# Button.net
KiCad netlist of a schematic drawn in Altium Designer
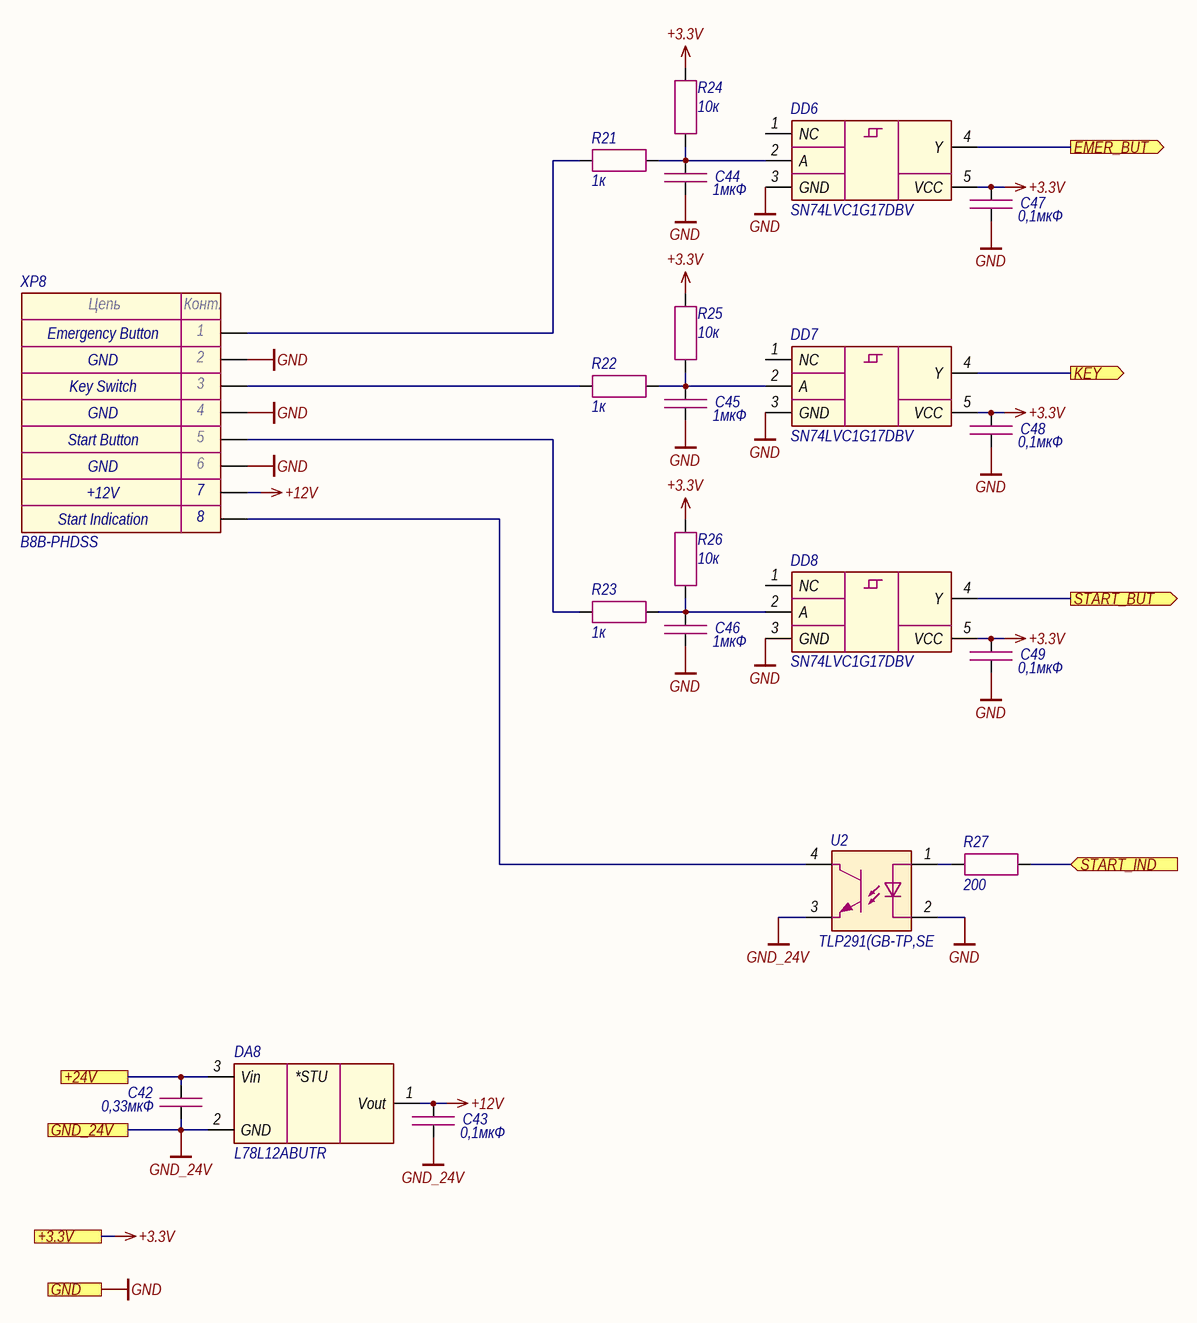
[diagram p0: Button.SchDoc]

(export (version "E")
  (design (tool "Eeschema 10.0.6"))
  (components
    (comp (ref "C42")
      (value "0,33мкФ")
      (footprint "Pcb_library:CAP_0805")
      (fields (field (name "MANUFACTURER") "Murata"))
      (libsource (lib "Schem_library") (part "Capacitor"))
    )
    (comp (ref "C43")
      (value "0,1мкФ")
      (footprint "Pcb_library:CAP_0603")
      (fields (field (name "MANUFACTURER") "Murata"))
      (libsource (lib "Schem_library") (part "Capacitor"))
    )
    (comp (ref "C44")
      (value "1мкФ")
      (footprint "Pcb_library:CAP_0603")
      (fields (field (name "MANUFACTURER") "Murata"))
      (libsource (lib "Schem_library") (part "Capacitor"))
    )
    (comp (ref "C45")
      (value "1мкФ")
      (footprint "Pcb_library:CAP_0603")
      (fields (field (name "MANUFACTURER") "Murata"))
      (libsource (lib "Schem_library") (part "Capacitor"))
    )
    (comp (ref "C46")
      (value "1мкФ")
      (footprint "Pcb_library:CAP_0603")
      (fields (field (name "MANUFACTURER") "Murata"))
      (libsource (lib "Schem_library") (part "Capacitor"))
    )
    (comp (ref "C47")
      (value "0,1мкФ")
      (footprint "Pcb_library:CAP_0603")
      (fields (field (name "MANUFACTURER") "Murata"))
      (libsource (lib "Schem_library") (part "Capacitor"))
    )
    (comp (ref "C48")
      (value "0,1мкФ")
      (footprint "Pcb_library:CAP_0603")
      (fields (field (name "MANUFACTURER") "Murata"))
      (libsource (lib "Schem_library") (part "Capacitor"))
    )
    (comp (ref "C49")
      (value "0,1мкФ")
      (footprint "Pcb_library:CAP_0603")
      (fields (field (name "MANUFACTURER") "Murata"))
      (libsource (lib "Schem_library") (part "Capacitor"))
    )
    (comp (ref "DA8")
      (value "L78L12ABUTR")
      (footprint "Pcb_library:SOT-89")
      (fields (field (name "MANUFACTURER") "STMicroelectronics"))
      (libsource (lib "Schem_library") (part "LD2981ABU50TR"))
    )
    (comp (ref "DD6")
      (value "SN74LVC1G17DBV")
      (footprint "Pcb_library:SOT-23-5")
      (fields (field (name "MANUFACTURER") "Texas Instruments"))
      (libsource (lib "Schem_library") (part "SN74LVC1G17"))
    )
    (comp (ref "DD7")
      (value "SN74LVC1G17DBV")
      (footprint "Pcb_library:SOT-23-5")
      (fields (field (name "MANUFACTURER") "Texas Instruments"))
      (libsource (lib "Schem_library") (part "SN74LVC1G17"))
    )
    (comp (ref "DD8")
      (value "SN74LVC1G17DBV")
      (footprint "Pcb_library:SOT-23-5")
      (fields (field (name "MANUFACTURER") "Texas Instruments"))
      (libsource (lib "Schem_library") (part "SN74LVC1G17"))
    )
    (comp (ref "R21")
      (value "1к")
      (footprint "Pcb_library:RES_0603")
      (fields (field (name "MANUFACTURER") "Yageo"))
      (libsource (lib "Schem_library") (part "Resistor"))
    )
    (comp (ref "R22")
      (value "1к")
      (footprint "Pcb_library:RES_0603")
      (fields (field (name "MANUFACTURER") "Yageo"))
      (libsource (lib "Schem_library") (part "Resistor"))
    )
    (comp (ref "R23")
      (value "1к")
      (footprint "Pcb_library:RES_0603")
      (fields (field (name "MANUFACTURER") "Yageo"))
      (libsource (lib "Schem_library") (part "Resistor"))
    )
    (comp (ref "R24")
      (value "10к")
      (footprint "Pcb_library:RES_0603")
      (fields (field (name "MANUFACTURER") "Yageo"))
      (libsource (lib "Schem_library") (part "Resistor"))
    )
    (comp (ref "R25")
      (value "10к")
      (footprint "Pcb_library:RES_0603")
      (fields (field (name "MANUFACTURER") "Yageo"))
      (libsource (lib "Schem_library") (part "Resistor"))
    )
    (comp (ref "R26")
      (value "10к")
      (footprint "Pcb_library:RES_0603")
      (fields (field (name "MANUFACTURER") "Yageo"))
      (libsource (lib "Schem_library") (part "Resistor"))
    )
    (comp (ref "R27")
      (value "200")
      (footprint "Pcb_library:RES_0603")
      (fields (field (name "MANUFACTURER") "Yageo"))
      (libsource (lib "Schem_library") (part "Resistor"))
    )
    (comp (ref "U2")
      (value "TLP291(GB-TP,SE")
      (footprint "Pcb_library:11-3C1")
      (fields (field (name "MANUFACTURER") "Toshiba"))
      (libsource (lib "Schem_library") (part "TLP291"))
    )
    (comp (ref "XP8")
      (value "B8B-PHDSS")
      (footprint "Pcb_library:B8B-PHDSS")
      (fields (field (name "MANUFACTURER") "JST"))
      (libsource (lib "Schem_library") (part "Connector-8"))
    )
  )
  (nets
    (net (code "1") (name "+3.3V") (class "Default")
      (node (ref "C47") (pin "1") (pinfunction "1_1") (pintype "passive"))
      (node (ref "C48") (pin "1") (pinfunction "1_1") (pintype "passive"))
      (node (ref "C49") (pin "1") (pinfunction "1_1") (pintype "passive"))
      (node (ref "DD6") (pin "5") (pinfunction "VCC_5") (pintype "passive"))
      (node (ref "DD7") (pin "5") (pinfunction "VCC_5") (pintype "passive"))
      (node (ref "DD8") (pin "5") (pinfunction "VCC_5") (pintype "passive"))
      (node (ref "R24") (pin "2") (pinfunction "2_2") (pintype "passive"))
      (node (ref "R25") (pin "2") (pinfunction "2_2") (pintype "passive"))
      (node (ref "R26") (pin "2") (pinfunction "2_2") (pintype "passive"))
    )
    (net (code "2") (name "+12V") (class "Default")
      (node (ref "C43") (pin "1") (pinfunction "1_1") (pintype "passive"))
      (node (ref "DA8") (pin "1") (pinfunction "Vout_1") (pintype "passive"))
      (node (ref "XP8") (pin "7") (pintype "passive"))
    )
    (net (code "3") (name "/+24V") (class "Default")
      (node (ref "C42") (pin "2") (pinfunction "2_2") (pintype "passive"))
      (node (ref "DA8") (pin "3") (pinfunction "Vin_3") (pintype "passive"))
    )
    (net (code "4") (name "/EMER_BUT") (class "Default")
      (node (ref "DD6") (pin "4") (pinfunction "Y_4") (pintype "passive"))
    )
    (net (code "5") (name "/KEY") (class "Default")
      (node (ref "DD7") (pin "4") (pinfunction "Y_4") (pintype "passive"))
    )
    (net (code "6") (name "/START_BUT") (class "Default")
      (node (ref "DD8") (pin "4") (pinfunction "Y_4") (pintype "passive"))
    )
    (net (code "7") (name "/START_IND") (class "Default")
      (node (ref "R27") (pin "2") (pinfunction "2_2") (pintype "passive"))
    )
    (net (code "8") (name "GND") (class "Default")
      (node (ref "C44") (pin "2") (pinfunction "2_2") (pintype "passive"))
      (node (ref "C45") (pin "2") (pinfunction "2_2") (pintype "passive"))
      (node (ref "C46") (pin "2") (pinfunction "2_2") (pintype "passive"))
      (node (ref "C47") (pin "2") (pinfunction "2_2") (pintype "passive"))
      (node (ref "C48") (pin "2") (pinfunction "2_2") (pintype "passive"))
      (node (ref "C49") (pin "2") (pinfunction "2_2") (pintype "passive"))
      (node (ref "DD6") (pin "3") (pinfunction "GND_3") (pintype "passive"))
      (node (ref "DD7") (pin "3") (pinfunction "GND_3") (pintype "passive"))
      (node (ref "DD8") (pin "3") (pinfunction "GND_3") (pintype "passive"))
      (node (ref "U2") (pin "2") (pintype "passive"))
      (node (ref "XP8") (pin "2") (pintype "passive"))
      (node (ref "XP8") (pin "4") (pintype "passive"))
      (node (ref "XP8") (pin "6") (pintype "passive"))
    )
    (net (code "9") (name "GND_24V") (class "Default")
      (node (ref "C42") (pin "1") (pinfunction "1_1") (pintype "passive"))
      (node (ref "C43") (pin "2") (pinfunction "2_2") (pintype "passive"))
      (node (ref "DA8") (pin "2") (pinfunction "GND_2") (pintype "passive"))
      (node (ref "U2") (pin "3") (pintype "passive"))
    )
    (net (code "10") (name "Net-(DD6-A)") (class "Default")
      (node (ref "C44") (pin "1") (pinfunction "1_1") (pintype "passive"))
      (node (ref "DD6") (pin "2") (pinfunction "A_2") (pintype "passive"))
      (node (ref "R21") (pin "2") (pinfunction "2_2") (pintype "passive"))
      (node (ref "R24") (pin "1") (pinfunction "1_1") (pintype "passive"))
    )
    (net (code "11") (name "Net-(DD7-A)") (class "Default")
      (node (ref "C45") (pin "1") (pinfunction "1_1") (pintype "passive"))
      (node (ref "DD7") (pin "2") (pinfunction "A_2") (pintype "passive"))
      (node (ref "R22") (pin "2") (pinfunction "2_2") (pintype "passive"))
      (node (ref "R25") (pin "1") (pinfunction "1_1") (pintype "passive"))
    )
    (net (code "12") (name "Net-(DD8-A)") (class "Default")
      (node (ref "C46") (pin "1") (pinfunction "1_1") (pintype "passive"))
      (node (ref "DD8") (pin "2") (pinfunction "A_2") (pintype "passive"))
      (node (ref "R23") (pin "2") (pinfunction "2_2") (pintype "passive"))
      (node (ref "R26") (pin "1") (pinfunction "1_1") (pintype "passive"))
    )
    (net (code "13") (name "Net-(R21-Pad1)") (class "Default")
      (node (ref "R21") (pin "1") (pinfunction "1_1") (pintype "passive"))
      (node (ref "XP8") (pin "1") (pintype "passive"))
    )
    (net (code "14") (name "Net-(R22-Pad1)") (class "Default")
      (node (ref "R22") (pin "1") (pinfunction "1_1") (pintype "passive"))
      (node (ref "XP8") (pin "3") (pintype "passive"))
    )
    (net (code "15") (name "Net-(R23-Pad1)") (class "Default")
      (node (ref "R23") (pin "1") (pinfunction "1_1") (pintype "passive"))
      (node (ref "XP8") (pin "5") (pintype "passive"))
    )
    (net (code "16") (name "Net-(R27-Pad1)") (class "Default")
      (node (ref "R27") (pin "1") (pinfunction "1_1") (pintype "passive"))
      (node (ref "U2") (pin "1") (pintype "passive"))
    )
    (net (code "17") (name "Net-(U2-Pad4)") (class "Default")
      (node (ref "U2") (pin "4") (pintype "passive"))
      (node (ref "XP8") (pin "8") (pintype "passive"))
    )
    (net (code "18") (name "unconnected-(DD6-NC-Pad1)") (class "Default")
      (node (ref "DD6") (pin "1") (pinfunction "NC_1") (pintype "passive"))
    )
    (net (code "19") (name "unconnected-(DD7-NC-Pad1)") (class "Default")
      (node (ref "DD7") (pin "1") (pinfunction "NC_1") (pintype "passive"))
    )
    (net (code "20") (name "unconnected-(DD8-NC-Pad1)") (class "Default")
      (node (ref "DD8") (pin "1") (pinfunction "NC_1") (pintype "passive"))
    )
  )
)
